# Sentral.net
KiCad netlist of a schematic drawn in EAGLE
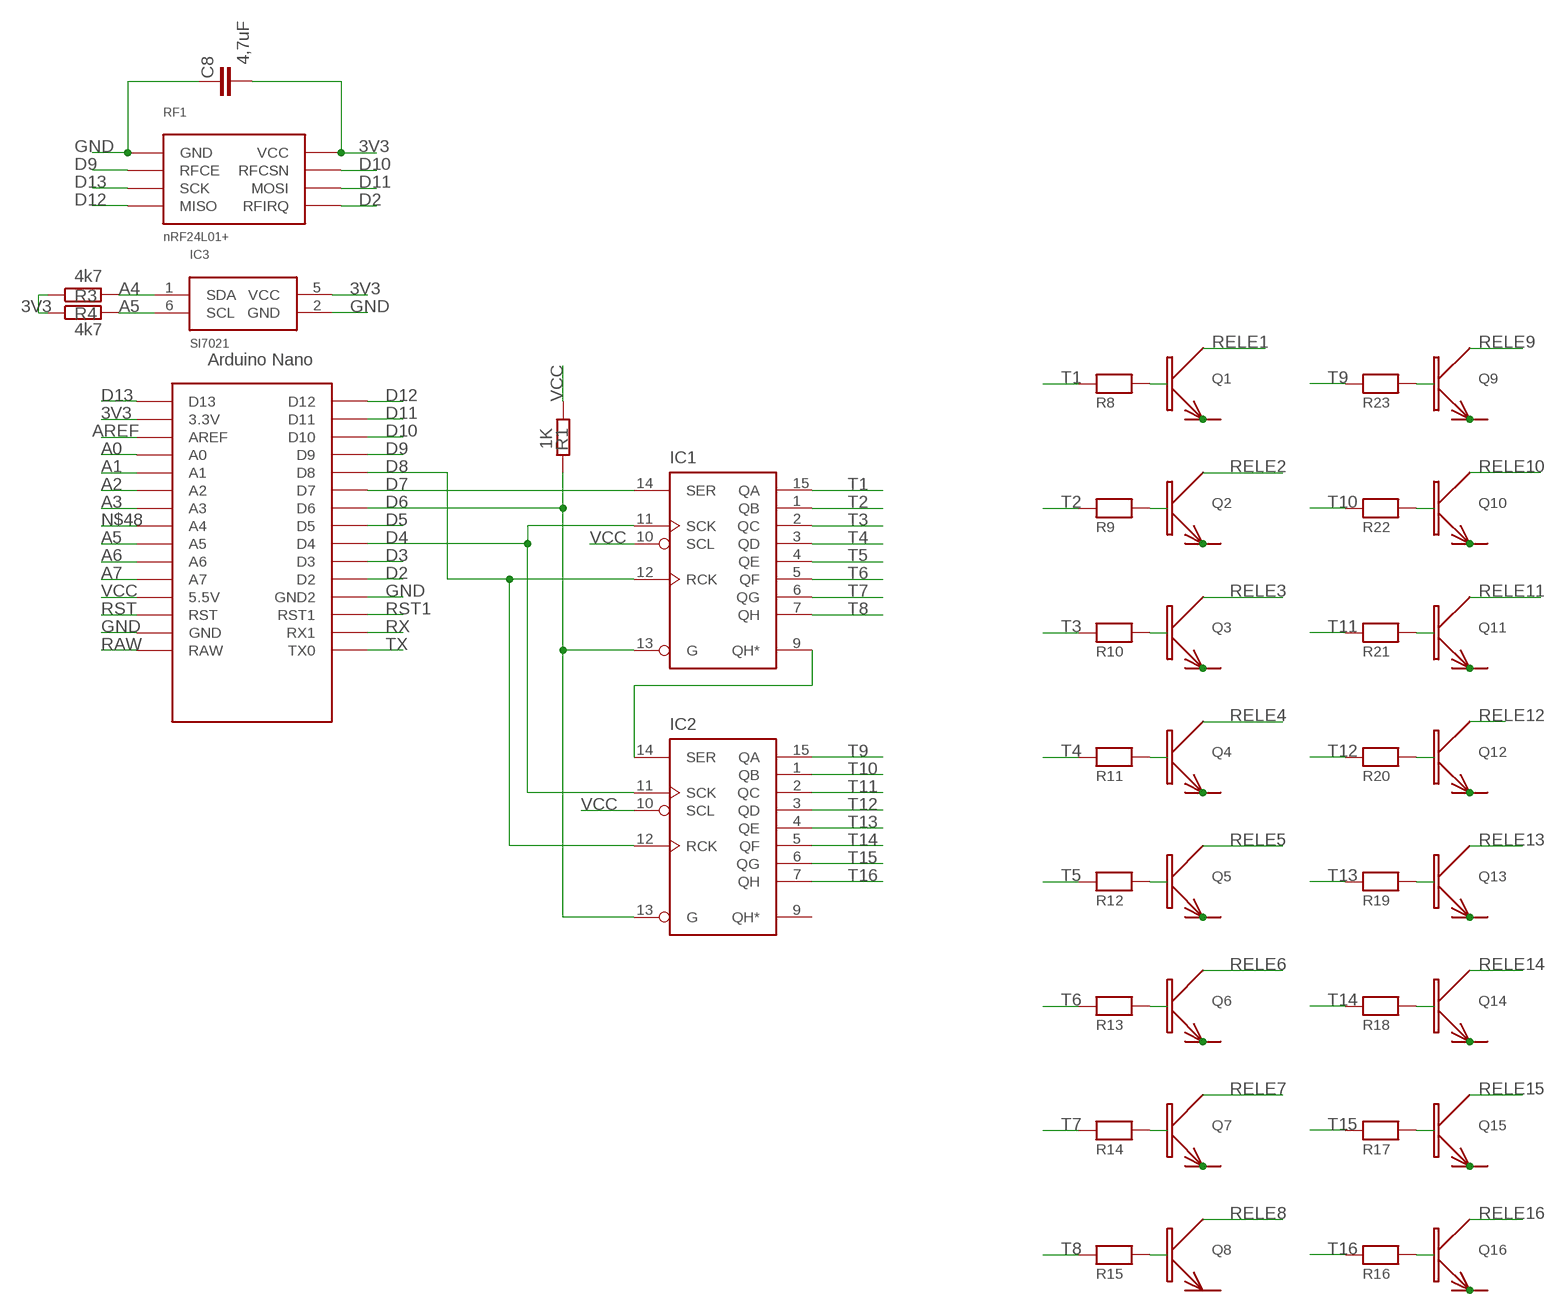
[diagram p0: schematic, sheet 1]
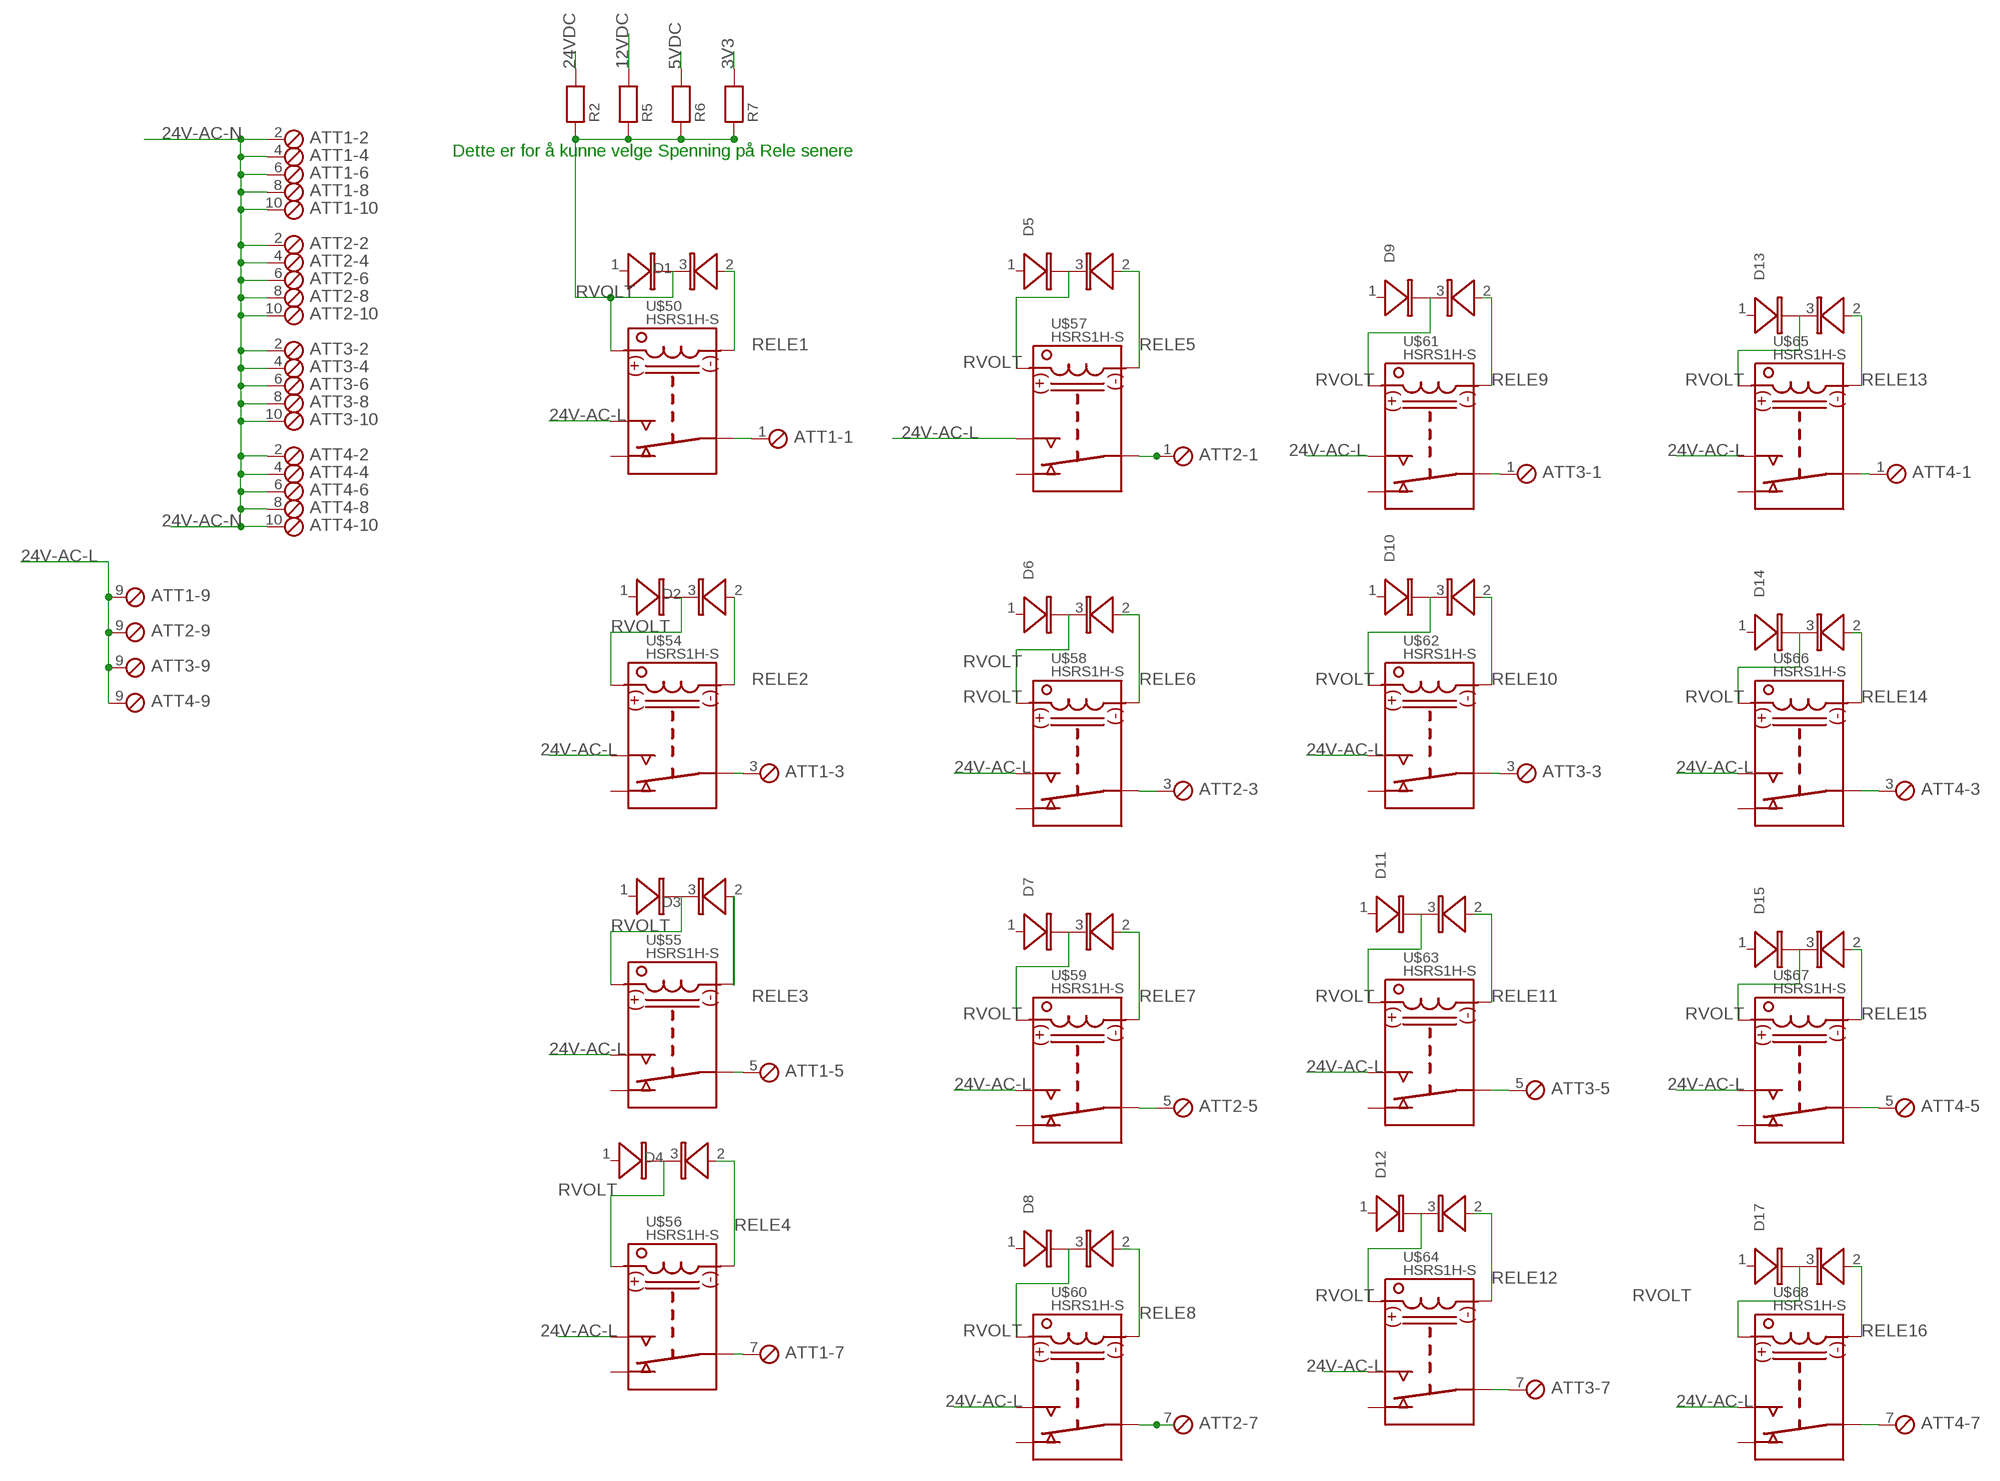
[diagram p1: schematic, sheet 2]

(export (version "E")
  (design (tool "Eeschema 10.0.6"))
  (components
    (comp (ref "C8")
      (value "4,7uF")
      (footprint "eagle-import:C4532")
      (libsource (lib "eagle-import") (part "C-EUC4532"))
    )
    (comp (ref "IC1")
      (value "74595")
      (footprint "eagle-import:SO-16")
      (libsource (lib "eagle-import") (part "74595"))
    )
    (comp (ref "IC2")
      (value "74595")
      (footprint "eagle-import:SO-16")
      (libsource (lib "eagle-import") (part "74595"))
    )
    (comp (ref "IC3")
      (value "SI7021")
      (footprint "eagle-import:DFN6")
      (libsource (lib "eagle-import") (part "SI7021"))
    )
    (comp (ref "Q1")
      (value "BC817")
      (footprint "eagle-import:SOT23")
      (libsource (lib "eagle-import") (part "BC817"))
    )
    (comp (ref "Q2")
      (value "BC817")
      (footprint "eagle-import:SOT23")
      (libsource (lib "eagle-import") (part "BC817"))
    )
    (comp (ref "Q3")
      (value "BC817")
      (footprint "eagle-import:SOT23")
      (libsource (lib "eagle-import") (part "BC817"))
    )
    (comp (ref "Q4")
      (value "BC817")
      (footprint "eagle-import:SOT23")
      (libsource (lib "eagle-import") (part "BC817"))
    )
    (comp (ref "Q5")
      (value "BC817")
      (footprint "eagle-import:SOT23")
      (libsource (lib "eagle-import") (part "BC817"))
    )
    (comp (ref "Q6")
      (value "BC817")
      (footprint "eagle-import:SOT23")
      (libsource (lib "eagle-import") (part "BC817"))
    )
    (comp (ref "Q7")
      (value "BC817")
      (footprint "eagle-import:SOT23")
      (libsource (lib "eagle-import") (part "BC817"))
    )
    (comp (ref "Q8")
      (value "BC817")
      (footprint "eagle-import:SOT23")
      (libsource (lib "eagle-import") (part "BC817"))
    )
    (comp (ref "Q9")
      (value "BC817")
      (footprint "eagle-import:SOT23")
      (libsource (lib "eagle-import") (part "BC817"))
    )
    (comp (ref "Q10")
      (value "BC817")
      (footprint "eagle-import:SOT23")
      (libsource (lib "eagle-import") (part "BC817"))
    )
    (comp (ref "Q11")
      (value "BC817")
      (footprint "eagle-import:SOT23")
      (libsource (lib "eagle-import") (part "BC817"))
    )
    (comp (ref "Q12")
      (value "BC817")
      (footprint "eagle-import:SOT23")
      (libsource (lib "eagle-import") (part "BC817"))
    )
    (comp (ref "Q13")
      (value "BC817")
      (footprint "eagle-import:SOT23")
      (libsource (lib "eagle-import") (part "BC817"))
    )
    (comp (ref "Q14")
      (value "BC817")
      (footprint "eagle-import:SOT23")
      (libsource (lib "eagle-import") (part "BC817"))
    )
    (comp (ref "Q15")
      (value "BC817")
      (footprint "eagle-import:SOT23")
      (libsource (lib "eagle-import") (part "BC817"))
    )
    (comp (ref "Q16")
      (value "BC817")
      (footprint "eagle-import:SOT23")
      (libsource (lib "eagle-import") (part "BC817"))
    )
    (comp (ref "R1")
      (value "1K")
      (footprint "eagle-import:R0805")
      (libsource (lib "eagle-import") (part "R-EU_R0805"))
    )
    (comp (ref "R3")
      (value "4k7")
      (footprint "eagle-import:R0805")
      (libsource (lib "eagle-import") (part "R-EU_R0805"))
    )
    (comp (ref "R4")
      (value "4k7")
      (footprint "eagle-import:R0805")
      (libsource (lib "eagle-import") (part "R-EU_R0805"))
    )
    (comp (ref "R8")
      (value "RES-A")
      (footprint "eagle-import:A")
      (libsource (lib "eagle-import") (part "RES-A"))
    )
    (comp (ref "R9")
      (value "RES-A")
      (footprint "eagle-import:A")
      (libsource (lib "eagle-import") (part "RES-A"))
    )
    (comp (ref "R10")
      (value "RES-A")
      (footprint "eagle-import:A")
      (libsource (lib "eagle-import") (part "RES-A"))
    )
    (comp (ref "R11")
      (value "RES-A")
      (footprint "eagle-import:A")
      (libsource (lib "eagle-import") (part "RES-A"))
    )
    (comp (ref "R12")
      (value "RES-A")
      (footprint "eagle-import:A")
      (libsource (lib "eagle-import") (part "RES-A"))
    )
    (comp (ref "R13")
      (value "RES-A")
      (footprint "eagle-import:A")
      (libsource (lib "eagle-import") (part "RES-A"))
    )
    (comp (ref "R14")
      (value "RES-A")
      (footprint "eagle-import:A")
      (libsource (lib "eagle-import") (part "RES-A"))
    )
    (comp (ref "R15")
      (value "RES-A")
      (footprint "eagle-import:A")
      (libsource (lib "eagle-import") (part "RES-A"))
    )
    (comp (ref "R16")
      (value "RES-A")
      (footprint "eagle-import:A")
      (libsource (lib "eagle-import") (part "RES-A"))
    )
    (comp (ref "R17")
      (value "RES-A")
      (footprint "eagle-import:A")
      (libsource (lib "eagle-import") (part "RES-A"))
    )
    (comp (ref "R18")
      (value "RES-A")
      (footprint "eagle-import:A")
      (libsource (lib "eagle-import") (part "RES-A"))
    )
    (comp (ref "R19")
      (value "RES-A")
      (footprint "eagle-import:A")
      (libsource (lib "eagle-import") (part "RES-A"))
    )
    (comp (ref "R20")
      (value "RES-A")
      (footprint "eagle-import:A")
      (libsource (lib "eagle-import") (part "RES-A"))
    )
    (comp (ref "R21")
      (value "RES-A")
      (footprint "eagle-import:A")
      (libsource (lib "eagle-import") (part "RES-A"))
    )
    (comp (ref "R22")
      (value "RES-A")
      (footprint "eagle-import:A")
      (libsource (lib "eagle-import") (part "RES-A"))
    )
    (comp (ref "R23")
      (value "RES-A")
      (footprint "eagle-import:A")
      (libsource (lib "eagle-import") (part "RES-A"))
    )
    (comp (ref "RF1")
      (value "nRF24L01+")
      (footprint "eagle-import:2X4-2.54MM")
      (libsource (lib "eagle-import") (part "NRF24L01"))
    )
    (comp (ref "U$1")
      (value "NANO")
      (footprint "eagle-import:NANO")
      (libsource (lib "eagle-import") (part "NANO"))
    )
    (comp (ref "ATT1")
      (value "MPT10")
      (footprint "eagle-import:10POL254")
      (libsource (lib "eagle-import") (part "MPT10"))
    )
    (comp (ref "ATT2")
      (value "MPT10")
      (footprint "eagle-import:10POL254")
      (libsource (lib "eagle-import") (part "MPT10"))
    )
    (comp (ref "ATT3")
      (value "MPT10")
      (footprint "eagle-import:10POL254")
      (libsource (lib "eagle-import") (part "MPT10"))
    )
    (comp (ref "ATT4")
      (value "MPT10")
      (footprint "eagle-import:10POL254")
      (libsource (lib "eagle-import") (part "MPT10"))
    )
    (comp (ref "D1")
      (value "BAV70")
      (footprint "eagle-import:SOT23")
      (libsource (lib "eagle-import") (part "BAV70"))
    )
    (comp (ref "D2")
      (value "BAV70")
      (footprint "eagle-import:SOT23")
      (libsource (lib "eagle-import") (part "BAV70"))
    )
    (comp (ref "D3")
      (value "BAV70")
      (footprint "eagle-import:SOT23")
      (libsource (lib "eagle-import") (part "BAV70"))
    )
    (comp (ref "D4")
      (value "BAV70")
      (footprint "eagle-import:SOT23")
      (libsource (lib "eagle-import") (part "BAV70"))
    )
    (comp (ref "D5")
      (value "BAV70")
      (footprint "eagle-import:SOT23")
      (libsource (lib "eagle-import") (part "BAV70"))
    )
    (comp (ref "D6")
      (value "BAV70")
      (footprint "eagle-import:SOT23")
      (libsource (lib "eagle-import") (part "BAV70"))
    )
    (comp (ref "D7")
      (value "BAV70")
      (footprint "eagle-import:SOT23")
      (libsource (lib "eagle-import") (part "BAV70"))
    )
    (comp (ref "D8")
      (value "BAV70")
      (footprint "eagle-import:SOT23")
      (libsource (lib "eagle-import") (part "BAV70"))
    )
    (comp (ref "D9")
      (value "BAV70")
      (footprint "eagle-import:SOT23")
      (libsource (lib "eagle-import") (part "BAV70"))
    )
    (comp (ref "D10")
      (value "BAV70")
      (footprint "eagle-import:SOT23")
      (libsource (lib "eagle-import") (part "BAV70"))
    )
    (comp (ref "D11")
      (value "BAV70")
      (footprint "eagle-import:SOT23")
      (libsource (lib "eagle-import") (part "BAV70"))
    )
    (comp (ref "D12")
      (value "BAV70")
      (footprint "eagle-import:SOT23")
      (libsource (lib "eagle-import") (part "BAV70"))
    )
    (comp (ref "D13")
      (value "BAV70")
      (footprint "eagle-import:SOT23")
      (libsource (lib "eagle-import") (part "BAV70"))
    )
    (comp (ref "D14")
      (value "BAV70")
      (footprint "eagle-import:SOT23")
      (libsource (lib "eagle-import") (part "BAV70"))
    )
    (comp (ref "D15")
      (value "BAV70")
      (footprint "eagle-import:SOT23")
      (libsource (lib "eagle-import") (part "BAV70"))
    )
    (comp (ref "D17")
      (value "BAV70")
      (footprint "eagle-import:SOT23")
      (libsource (lib "eagle-import") (part "BAV70"))
    )
    (comp (ref "R2")
      (value "RES-C")
      (footprint "eagle-import:C")
      (libsource (lib "eagle-import") (part "RES-C"))
    )
    (comp (ref "R5")
      (value "RES-C")
      (footprint "eagle-import:C")
      (libsource (lib "eagle-import") (part "RES-C"))
    )
    (comp (ref "R6")
      (value "RES-C")
      (footprint "eagle-import:C")
      (libsource (lib "eagle-import") (part "RES-C"))
    )
    (comp (ref "R7")
      (value "RES-C")
      (footprint "eagle-import:C")
      (libsource (lib "eagle-import") (part "RES-C"))
    )
    (comp (ref "U$50")
      (value "HSRS1H-S")
      (footprint "eagle-import:DIL12RLY")
      (libsource (lib "eagle-import") (part "HSRS1H-S"))
    )
    (comp (ref "U$54")
      (value "HSRS1H-S")
      (footprint "eagle-import:DIL12RLY")
      (libsource (lib "eagle-import") (part "HSRS1H-S"))
    )
    (comp (ref "U$55")
      (value "HSRS1H-S")
      (footprint "eagle-import:DIL12RLY")
      (libsource (lib "eagle-import") (part "HSRS1H-S"))
    )
    (comp (ref "U$56")
      (value "HSRS1H-S")
      (footprint "eagle-import:DIL12RLY")
      (libsource (lib "eagle-import") (part "HSRS1H-S"))
    )
    (comp (ref "U$57")
      (value "HSRS1H-S")
      (footprint "eagle-import:DIL12RLY")
      (libsource (lib "eagle-import") (part "HSRS1H-S"))
    )
    (comp (ref "U$58")
      (value "HSRS1H-S")
      (footprint "eagle-import:DIL12RLY")
      (libsource (lib "eagle-import") (part "HSRS1H-S"))
    )
    (comp (ref "U$59")
      (value "HSRS1H-S")
      (footprint "eagle-import:DIL12RLY")
      (libsource (lib "eagle-import") (part "HSRS1H-S"))
    )
    (comp (ref "U$60")
      (value "HSRS1H-S")
      (footprint "eagle-import:DIL12RLY")
      (libsource (lib "eagle-import") (part "HSRS1H-S"))
    )
    (comp (ref "U$61")
      (value "HSRS1H-S")
      (footprint "eagle-import:DIL12RLY")
      (libsource (lib "eagle-import") (part "HSRS1H-S"))
    )
    (comp (ref "U$62")
      (value "HSRS1H-S")
      (footprint "eagle-import:DIL12RLY")
      (libsource (lib "eagle-import") (part "HSRS1H-S"))
    )
    (comp (ref "U$63")
      (value "HSRS1H-S")
      (footprint "eagle-import:DIL12RLY")
      (libsource (lib "eagle-import") (part "HSRS1H-S"))
    )
    (comp (ref "U$64")
      (value "HSRS1H-S")
      (footprint "eagle-import:DIL12RLY")
      (libsource (lib "eagle-import") (part "HSRS1H-S"))
    )
    (comp (ref "U$65")
      (value "HSRS1H-S")
      (footprint "eagle-import:DIL12RLY")
      (libsource (lib "eagle-import") (part "HSRS1H-S"))
    )
    (comp (ref "U$66")
      (value "HSRS1H-S")
      (footprint "eagle-import:DIL12RLY")
      (libsource (lib "eagle-import") (part "HSRS1H-S"))
    )
    (comp (ref "U$67")
      (value "HSRS1H-S")
      (footprint "eagle-import:DIL12RLY")
      (libsource (lib "eagle-import") (part "HSRS1H-S"))
    )
    (comp (ref "U$68")
      (value "HSRS1H-S")
      (footprint "eagle-import:DIL12RLY")
      (libsource (lib "eagle-import") (part "HSRS1H-S"))
    )
  )
  (nets
    (net (code "1") (name "3V3") (class "Default")
      (node (ref "C8") (pin "1") (pinfunction "1_1") (pintype "passive"))
      (node (ref "IC3") (pin "5") (pinfunction "VCC_5") (pintype "bidirectional"))
      (node (ref "R3") (pin "1") (pinfunction "1_1") (pintype "passive"))
      (node (ref "R4") (pin "1") (pinfunction "1_1") (pintype "passive"))
      (node (ref "R7") (pin "2") (pinfunction "2_2") (pintype "passive"))
      (node (ref "RF1") (pin "P$2") (pinfunction "VCC_P$2") (pintype "power_in"))
      (node (ref "U$1") (pin "3.3V") (pinfunction "3.3V_3.3V") (pintype "bidirectional"))
    )
    (net (code "2") (name "5VDC") (class "Default")
      (node (ref "R6") (pin "2") (pinfunction "2_2") (pintype "passive"))
    )
    (net (code "3") (name "12VDC") (class "Default")
      (node (ref "R5") (pin "2") (pinfunction "2_2") (pintype "passive"))
    )
    (net (code "4") (name "24V-AC-L") (class "Default")
      (node (ref "ATT1") (pin "9") (pinfunction "1_9") (pintype "passive"))
      (node (ref "ATT2") (pin "9") (pinfunction "1_9") (pintype "passive"))
      (node (ref "ATT3") (pin "9") (pinfunction "1_9") (pintype "passive"))
      (node (ref "ATT4") (pin "9") (pinfunction "1_9") (pintype "passive"))
      (node (ref "U$50") (pin "1") (pinfunction "1_1") (pintype "passive"))
      (node (ref "U$54") (pin "1") (pinfunction "1_1") (pintype "passive"))
      (node (ref "U$55") (pin "1") (pinfunction "1_1") (pintype "passive"))
      (node (ref "U$56") (pin "1") (pinfunction "1_1") (pintype "passive"))
      (node (ref "U$57") (pin "1") (pinfunction "1_1") (pintype "passive"))
      (node (ref "U$58") (pin "1") (pinfunction "1_1") (pintype "passive"))
      (node (ref "U$59") (pin "1") (pinfunction "1_1") (pintype "passive"))
      (node (ref "U$60") (pin "1") (pinfunction "1_1") (pintype "passive"))
      (node (ref "U$61") (pin "1") (pinfunction "1_1") (pintype "passive"))
      (node (ref "U$62") (pin "1") (pinfunction "1_1") (pintype "passive"))
      (node (ref "U$63") (pin "1") (pinfunction "1_1") (pintype "passive"))
      (node (ref "U$64") (pin "1") (pinfunction "1_1") (pintype "passive"))
      (node (ref "U$65") (pin "1") (pinfunction "1_1") (pintype "passive"))
      (node (ref "U$66") (pin "1") (pinfunction "1_1") (pintype "passive"))
      (node (ref "U$67") (pin "1") (pinfunction "1_1") (pintype "passive"))
      (node (ref "U$68") (pin "1") (pinfunction "1_1") (pintype "passive"))
    )
    (net (code "5") (name "24V-AC-N") (class "Default")
      (node (ref "ATT1") (pin "10") (pinfunction "1_10") (pintype "passive"))
      (node (ref "ATT1") (pin "2") (pinfunction "1_2") (pintype "passive"))
      (node (ref "ATT1") (pin "4") (pinfunction "1_4") (pintype "passive"))
      (node (ref "ATT1") (pin "6") (pinfunction "1_6") (pintype "passive"))
      (node (ref "ATT1") (pin "8") (pinfunction "1_8") (pintype "passive"))
      (node (ref "ATT2") (pin "10") (pinfunction "1_10") (pintype "passive"))
      (node (ref "ATT2") (pin "2") (pinfunction "1_2") (pintype "passive"))
      (node (ref "ATT2") (pin "4") (pinfunction "1_4") (pintype "passive"))
      (node (ref "ATT2") (pin "6") (pinfunction "1_6") (pintype "passive"))
      (node (ref "ATT2") (pin "8") (pinfunction "1_8") (pintype "passive"))
      (node (ref "ATT3") (pin "10") (pinfunction "1_10") (pintype "passive"))
      (node (ref "ATT3") (pin "2") (pinfunction "1_2") (pintype "passive"))
      (node (ref "ATT3") (pin "4") (pinfunction "1_4") (pintype "passive"))
      (node (ref "ATT3") (pin "6") (pinfunction "1_6") (pintype "passive"))
      (node (ref "ATT3") (pin "8") (pinfunction "1_8") (pintype "passive"))
      (node (ref "ATT4") (pin "10") (pinfunction "1_10") (pintype "passive"))
      (node (ref "ATT4") (pin "2") (pinfunction "1_2") (pintype "passive"))
      (node (ref "ATT4") (pin "4") (pinfunction "1_4") (pintype "passive"))
      (node (ref "ATT4") (pin "6") (pinfunction "1_6") (pintype "passive"))
      (node (ref "ATT4") (pin "8") (pinfunction "1_8") (pintype "passive"))
    )
    (net (code "6") (name "24VDC") (class "Default")
      (node (ref "R2") (pin "2") (pinfunction "2_2") (pintype "passive"))
    )
    (net (code "7") (name "A0") (class "Default")
      (node (ref "U$1") (pin "A0") (pinfunction "A0_A0") (pintype "bidirectional"))
    )
    (net (code "8") (name "A1") (class "Default")
      (node (ref "U$1") (pin "A1") (pinfunction "A1_A1") (pintype "bidirectional"))
    )
    (net (code "9") (name "A2") (class "Default")
      (node (ref "U$1") (pin "A2") (pinfunction "A2_A2") (pintype "bidirectional"))
    )
    (net (code "10") (name "A3") (class "Default")
      (node (ref "U$1") (pin "A3") (pinfunction "A3_A3") (pintype "bidirectional"))
    )
    (net (code "11") (name "A4") (class "Default")
      (node (ref "IC3") (pin "1") (pinfunction "SDA_1") (pintype "bidirectional"))
      (node (ref "R3") (pin "2") (pinfunction "2_2") (pintype "passive"))
    )
    (net (code "12") (name "A5") (class "Default")
      (node (ref "IC3") (pin "6") (pinfunction "SCL_6") (pintype "bidirectional"))
      (node (ref "R4") (pin "2") (pinfunction "2_2") (pintype "passive"))
      (node (ref "U$1") (pin "A5") (pinfunction "A5_A5") (pintype "bidirectional"))
    )
    (net (code "13") (name "A6") (class "Default")
      (node (ref "U$1") (pin "A6") (pinfunction "A6_A6") (pintype "bidirectional"))
    )
    (net (code "14") (name "A7") (class "Default")
      (node (ref "U$1") (pin "A7") (pinfunction "A7_A7") (pintype "bidirectional"))
    )
    (net (code "15") (name "AREF") (class "Default")
      (node (ref "U$1") (pin "AREF") (pinfunction "AREF_AREF") (pintype "bidirectional"))
    )
    (net (code "16") (name "D2") (class "Default")
      (node (ref "RF1") (pin "P$8") (pinfunction "RFIRQ_P$8") (pintype "output"))
      (node (ref "U$1") (pin "D2") (pinfunction "D2_D2") (pintype "bidirectional"))
    )
    (net (code "17") (name "D3") (class "Default")
      (node (ref "U$1") (pin "D3") (pinfunction "D3_D3") (pintype "bidirectional"))
    )
    (net (code "18") (name "D4") (class "Default")
      (node (ref "IC1") (pin "11") (pinfunction "SCK_11") (pintype "input"))
      (node (ref "IC2") (pin "11") (pinfunction "SCK_11") (pintype "input"))
      (node (ref "U$1") (pin "D4") (pinfunction "D4_D4") (pintype "bidirectional"))
    )
    (net (code "19") (name "D5") (class "Default")
      (node (ref "U$1") (pin "D5") (pinfunction "D5_D5") (pintype "bidirectional"))
    )
    (net (code "20") (name "D6") (class "Default")
      (node (ref "IC1") (pin "13") (pinfunction "G_13") (pintype "input"))
      (node (ref "IC2") (pin "13") (pinfunction "G_13") (pintype "input"))
      (node (ref "R1") (pin "2") (pinfunction "2_2") (pintype "passive"))
      (node (ref "U$1") (pin "D6") (pinfunction "D6_D6") (pintype "bidirectional"))
    )
    (net (code "21") (name "D7") (class "Default")
      (node (ref "IC1") (pin "14") (pinfunction "SER_14") (pintype "input"))
      (node (ref "U$1") (pin "D7") (pinfunction "D7_D7") (pintype "bidirectional"))
    )
    (net (code "22") (name "D8") (class "Default")
      (node (ref "IC1") (pin "12") (pinfunction "RCK_12") (pintype "input"))
      (node (ref "IC2") (pin "12") (pinfunction "RCK_12") (pintype "input"))
      (node (ref "U$1") (pin "D8") (pinfunction "D8_D8") (pintype "bidirectional"))
    )
    (net (code "23") (name "D9") (class "Default")
      (node (ref "RF1") (pin "P$3") (pinfunction "RFCE_P$3") (pintype "input"))
      (node (ref "U$1") (pin "D9") (pinfunction "D9_D9") (pintype "bidirectional"))
    )
    (net (code "24") (name "D10") (class "Default")
      (node (ref "RF1") (pin "P$4") (pinfunction "RFCSN_P$4") (pintype "bidirectional"))
      (node (ref "U$1") (pin "D10") (pinfunction "D10_D10") (pintype "bidirectional"))
    )
    (net (code "25") (name "D11") (class "Default")
      (node (ref "RF1") (pin "P$6") (pinfunction "MOSI_P$6") (pintype "bidirectional"))
      (node (ref "U$1") (pin "D11") (pinfunction "D11_D11") (pintype "bidirectional"))
    )
    (net (code "26") (name "D12") (class "Default")
      (node (ref "RF1") (pin "P$7") (pinfunction "MISO_P$7") (pintype "bidirectional"))
      (node (ref "U$1") (pin "D12") (pinfunction "D12_D12") (pintype "bidirectional"))
    )
    (net (code "27") (name "D13") (class "Default")
      (node (ref "RF1") (pin "P$5") (pinfunction "SCK_P$5") (pintype "input"))
      (node (ref "U$1") (pin "D13") (pinfunction "D13_D13") (pintype "bidirectional"))
    )
    (net (code "28") (name "GND") (class "Default")
      (node (ref "C8") (pin "2") (pinfunction "2_2") (pintype "passive"))
      (node (ref "IC3") (pin "2") (pinfunction "GND_2") (pintype "bidirectional"))
      (node (ref "Q1") (pin "1") (pinfunction "E_1") (pintype "passive"))
      (node (ref "Q10") (pin "1") (pinfunction "E_1") (pintype "passive"))
      (node (ref "Q11") (pin "1") (pinfunction "E_1") (pintype "passive"))
      (node (ref "Q12") (pin "1") (pinfunction "E_1") (pintype "passive"))
      (node (ref "Q13") (pin "1") (pinfunction "E_1") (pintype "passive"))
      (node (ref "Q14") (pin "1") (pinfunction "E_1") (pintype "passive"))
      (node (ref "Q15") (pin "1") (pinfunction "E_1") (pintype "passive"))
      (node (ref "Q16") (pin "1") (pinfunction "E_1") (pintype "passive"))
      (node (ref "Q2") (pin "1") (pinfunction "E_1") (pintype "passive"))
      (node (ref "Q3") (pin "1") (pinfunction "E_1") (pintype "passive"))
      (node (ref "Q4") (pin "1") (pinfunction "E_1") (pintype "passive"))
      (node (ref "Q5") (pin "1") (pinfunction "E_1") (pintype "passive"))
      (node (ref "Q6") (pin "1") (pinfunction "E_1") (pintype "passive"))
      (node (ref "Q7") (pin "1") (pinfunction "E_1") (pintype "passive"))
      (node (ref "Q8") (pin "1") (pinfunction "E_1") (pintype "passive"))
      (node (ref "Q9") (pin "1") (pinfunction "E_1") (pintype "passive"))
      (node (ref "RF1") (pin "P$1") (pinfunction "GND_P$1") (pintype "power_in"))
      (node (ref "U$1") (pin "GND") (pinfunction "GND_GND") (pintype "bidirectional"))
      (node (ref "U$1") (pin "GND1") (pinfunction "GND2_GND1") (pintype "bidirectional"))
    )
    (net (code "29") (name "N$48") (class "Default")
      (node (ref "U$1") (pin "A4") (pinfunction "A4_A4") (pintype "bidirectional"))
    )
    (net (code "30") (name "Net-(ATT1-Pad1)") (class "Default")
      (node (ref "ATT1") (pin "1") (pinfunction "1_1") (pintype "passive"))
      (node (ref "U$50") (pin "6") (pinfunction "6,7_6") (pintype "passive"))
      (node (ref "U$50") (pin "7") (pinfunction "6,7_7") (pintype "passive"))
    )
    (net (code "31") (name "Net-(ATT1D-1)") (class "Default")
      (node (ref "ATT1") (pin "3") (pinfunction "1_3") (pintype "passive"))
      (node (ref "U$54") (pin "6") (pinfunction "6,7_6") (pintype "passive"))
      (node (ref "U$54") (pin "7") (pinfunction "6,7_7") (pintype "passive"))
    )
    (net (code "32") (name "Net-(ATT1F-1)") (class "Default")
      (node (ref "ATT1") (pin "5") (pinfunction "1_5") (pintype "passive"))
      (node (ref "U$55") (pin "6") (pinfunction "6,7_6") (pintype "passive"))
      (node (ref "U$55") (pin "7") (pinfunction "6,7_7") (pintype "passive"))
    )
    (net (code "33") (name "Net-(ATT1H-1)") (class "Default")
      (node (ref "ATT1") (pin "7") (pinfunction "1_7") (pintype "passive"))
      (node (ref "U$56") (pin "6") (pinfunction "6,7_6") (pintype "passive"))
      (node (ref "U$56") (pin "7") (pinfunction "6,7_7") (pintype "passive"))
    )
    (net (code "34") (name "Net-(ATT2-Pad1)") (class "Default")
      (node (ref "ATT2") (pin "1") (pinfunction "1_1") (pintype "passive"))
      (node (ref "U$57") (pin "6") (pinfunction "6,7_6") (pintype "passive"))
      (node (ref "U$57") (pin "7") (pinfunction "6,7_7") (pintype "passive"))
    )
    (net (code "35") (name "Net-(ATT2D-1)") (class "Default")
      (node (ref "ATT2") (pin "3") (pinfunction "1_3") (pintype "passive"))
      (node (ref "U$58") (pin "6") (pinfunction "6,7_6") (pintype "passive"))
      (node (ref "U$58") (pin "7") (pinfunction "6,7_7") (pintype "passive"))
    )
    (net (code "36") (name "Net-(ATT2F-1)") (class "Default")
      (node (ref "ATT2") (pin "5") (pinfunction "1_5") (pintype "passive"))
      (node (ref "U$59") (pin "6") (pinfunction "6,7_6") (pintype "passive"))
      (node (ref "U$59") (pin "7") (pinfunction "6,7_7") (pintype "passive"))
    )
    (net (code "37") (name "Net-(ATT2H-1)") (class "Default")
      (node (ref "ATT2") (pin "7") (pinfunction "1_7") (pintype "passive"))
      (node (ref "U$60") (pin "6") (pinfunction "6,7_6") (pintype "passive"))
      (node (ref "U$60") (pin "7") (pinfunction "6,7_7") (pintype "passive"))
    )
    (net (code "38") (name "Net-(ATT3-Pad1)") (class "Default")
      (node (ref "ATT3") (pin "1") (pinfunction "1_1") (pintype "passive"))
      (node (ref "U$61") (pin "6") (pinfunction "6,7_6") (pintype "passive"))
      (node (ref "U$61") (pin "7") (pinfunction "6,7_7") (pintype "passive"))
    )
    (net (code "39") (name "Net-(ATT3D-1)") (class "Default")
      (node (ref "ATT3") (pin "3") (pinfunction "1_3") (pintype "passive"))
      (node (ref "U$62") (pin "6") (pinfunction "6,7_6") (pintype "passive"))
      (node (ref "U$62") (pin "7") (pinfunction "6,7_7") (pintype "passive"))
    )
    (net (code "40") (name "Net-(ATT3F-1)") (class "Default")
      (node (ref "ATT3") (pin "5") (pinfunction "1_5") (pintype "passive"))
      (node (ref "U$63") (pin "6") (pinfunction "6,7_6") (pintype "passive"))
      (node (ref "U$63") (pin "7") (pinfunction "6,7_7") (pintype "passive"))
    )
    (net (code "41") (name "Net-(ATT3H-1)") (class "Default")
      (node (ref "ATT3") (pin "7") (pinfunction "1_7") (pintype "passive"))
      (node (ref "U$64") (pin "6") (pinfunction "6,7_6") (pintype "passive"))
      (node (ref "U$64") (pin "7") (pinfunction "6,7_7") (pintype "passive"))
    )
    (net (code "42") (name "Net-(ATT4-Pad1)") (class "Default")
      (node (ref "ATT4") (pin "1") (pinfunction "1_1") (pintype "passive"))
      (node (ref "U$65") (pin "6") (pinfunction "6,7_6") (pintype "passive"))
      (node (ref "U$65") (pin "7") (pinfunction "6,7_7") (pintype "passive"))
    )
    (net (code "43") (name "Net-(ATT4D-1)") (class "Default")
      (node (ref "ATT4") (pin "3") (pinfunction "1_3") (pintype "passive"))
      (node (ref "U$66") (pin "6") (pinfunction "6,7_6") (pintype "passive"))
      (node (ref "U$66") (pin "7") (pinfunction "6,7_7") (pintype "passive"))
    )
    (net (code "44") (name "Net-(ATT4F-1)") (class "Default")
      (node (ref "ATT4") (pin "5") (pinfunction "1_5") (pintype "passive"))
      (node (ref "U$67") (pin "6") (pinfunction "6,7_6") (pintype "passive"))
      (node (ref "U$67") (pin "7") (pinfunction "6,7_7") (pintype "passive"))
    )
    (net (code "45") (name "Net-(ATT4H-1)") (class "Default")
      (node (ref "ATT4") (pin "7") (pinfunction "1_7") (pintype "passive"))
      (node (ref "U$68") (pin "6") (pinfunction "6,7_6") (pintype "passive"))
      (node (ref "U$68") (pin "7") (pinfunction "6,7_7") (pintype "passive"))
    )
    (net (code "46") (name "Net-(IC1A-QH*)") (class "Default")
      (node (ref "IC1") (pin "9") (pinfunction "QH*_9") (pintype "tri_state"))
      (node (ref "IC2") (pin "14") (pinfunction "SER_14") (pintype "input"))
    )
    (net (code "47") (name "Net-(Q1-B)") (class "Default")
      (node (ref "Q1") (pin "2") (pinfunction "B_2") (pintype "passive"))
      (node (ref "R8") (pin "2") (pinfunction "2_2") (pintype "passive"))
    )
    (net (code "48") (name "Net-(Q2-B)") (class "Default")
      (node (ref "Q2") (pin "2") (pinfunction "B_2") (pintype "passive"))
      (node (ref "R9") (pin "2") (pinfunction "2_2") (pintype "passive"))
    )
    (net (code "49") (name "Net-(Q3-B)") (class "Default")
      (node (ref "Q3") (pin "2") (pinfunction "B_2") (pintype "passive"))
      (node (ref "R10") (pin "2") (pinfunction "2_2") (pintype "passive"))
    )
    (net (code "50") (name "Net-(Q4-B)") (class "Default")
      (node (ref "Q4") (pin "2") (pinfunction "B_2") (pintype "passive"))
      (node (ref "R11") (pin "2") (pinfunction "2_2") (pintype "passive"))
    )
    (net (code "51") (name "Net-(Q5-B)") (class "Default")
      (node (ref "Q5") (pin "2") (pinfunction "B_2") (pintype "passive"))
      (node (ref "R12") (pin "2") (pinfunction "2_2") (pintype "passive"))
    )
    (net (code "52") (name "Net-(Q6-B)") (class "Default")
      (node (ref "Q6") (pin "2") (pinfunction "B_2") (pintype "passive"))
      (node (ref "R13") (pin "2") (pinfunction "2_2") (pintype "passive"))
    )
    (net (code "53") (name "Net-(Q7-B)") (class "Default")
      (node (ref "Q7") (pin "2") (pinfunction "B_2") (pintype "passive"))
      (node (ref "R14") (pin "2") (pinfunction "2_2") (pintype "passive"))
    )
    (net (code "54") (name "Net-(Q8-B)") (class "Default")
      (node (ref "Q8") (pin "2") (pinfunction "B_2") (pintype "passive"))
      (node (ref "R15") (pin "2") (pinfunction "2_2") (pintype "passive"))
    )
    (net (code "55") (name "Net-(Q9-B)") (class "Default")
      (node (ref "Q9") (pin "2") (pinfunction "B_2") (pintype "passive"))
      (node (ref "R23") (pin "2") (pinfunction "2_2") (pintype "passive"))
    )
    (net (code "56") (name "Net-(Q10-B)") (class "Default")
      (node (ref "Q10") (pin "2") (pinfunction "B_2") (pintype "passive"))
      (node (ref "R22") (pin "2") (pinfunction "2_2") (pintype "passive"))
    )
    (net (code "57") (name "Net-(Q11-B)") (class "Default")
      (node (ref "Q11") (pin "2") (pinfunction "B_2") (pintype "passive"))
      (node (ref "R21") (pin "2") (pinfunction "2_2") (pintype "passive"))
    )
    (net (code "58") (name "Net-(Q12-B)") (class "Default")
      (node (ref "Q12") (pin "2") (pinfunction "B_2") (pintype "passive"))
      (node (ref "R20") (pin "2") (pinfunction "2_2") (pintype "passive"))
    )
    (net (code "59") (name "Net-(Q13-B)") (class "Default")
      (node (ref "Q13") (pin "2") (pinfunction "B_2") (pintype "passive"))
      (node (ref "R19") (pin "2") (pinfunction "2_2") (pintype "passive"))
    )
    (net (code "60") (name "Net-(Q14-B)") (class "Default")
      (node (ref "Q14") (pin "2") (pinfunction "B_2") (pintype "passive"))
      (node (ref "R18") (pin "2") (pinfunction "2_2") (pintype "passive"))
    )
    (net (code "61") (name "Net-(Q15-B)") (class "Default")
      (node (ref "Q15") (pin "2") (pinfunction "B_2") (pintype "passive"))
      (node (ref "R17") (pin "2") (pinfunction "2_2") (pintype "passive"))
    )
    (net (code "62") (name "Net-(Q16-B)") (class "Default")
      (node (ref "Q16") (pin "2") (pinfunction "B_2") (pintype "passive"))
      (node (ref "R16") (pin "2") (pinfunction "2_2") (pintype "passive"))
    )
    (net (code "63") (name "RAW") (class "Default")
      (node (ref "U$1") (pin "RAW") (pinfunction "RAW_RAW") (pintype "bidirectional"))
    )
    (net (code "64") (name "RELE1") (class "Default")
      (node (ref "D1") (pin "2") (pinfunction "A2_2") (pintype "passive"))
      (node (ref "Q1") (pin "3") (pinfunction "C_3") (pintype "passive"))
      (node (ref "U$50") (pin "11") (pinfunction "11_11") (pintype "passive"))
    )
    (net (code "65") (name "RELE2") (class "Default")
      (node (ref "D2") (pin "2") (pinfunction "A2_2") (pintype "passive"))
      (node (ref "Q2") (pin "3") (pinfunction "C_3") (pintype "passive"))
      (node (ref "U$54") (pin "11") (pinfunction "11_11") (pintype "passive"))
    )
    (net (code "66") (name "RELE3") (class "Default")
      (node (ref "D3") (pin "2") (pinfunction "A2_2") (pintype "passive"))
      (node (ref "Q3") (pin "3") (pinfunction "C_3") (pintype "passive"))
      (node (ref "U$55") (pin "11") (pinfunction "11_11") (pintype "passive"))
    )
    (net (code "67") (name "RELE4") (class "Default")
      (node (ref "D4") (pin "2") (pinfunction "A2_2") (pintype "passive"))
      (node (ref "Q4") (pin "3") (pinfunction "C_3") (pintype "passive"))
      (node (ref "U$56") (pin "11") (pinfunction "11_11") (pintype "passive"))
    )
    (net (code "68") (name "RELE5") (class "Default")
      (node (ref "D5") (pin "2") (pinfunction "A2_2") (pintype "passive"))
      (node (ref "Q5") (pin "3") (pinfunction "C_3") (pintype "passive"))
      (node (ref "U$57") (pin "11") (pinfunction "11_11") (pintype "passive"))
    )
    (net (code "69") (name "RELE6") (class "Default")
      (node (ref "D6") (pin "2") (pinfunction "A2_2") (pintype "passive"))
      (node (ref "Q6") (pin "3") (pinfunction "C_3") (pintype "passive"))
      (node (ref "U$58") (pin "11") (pinfunction "11_11") (pintype "passive"))
    )
    (net (code "70") (name "RELE7") (class "Default")
      (node (ref "D7") (pin "2") (pinfunction "A2_2") (pintype "passive"))
      (node (ref "Q7") (pin "3") (pinfunction "C_3") (pintype "passive"))
      (node (ref "U$59") (pin "11") (pinfunction "11_11") (pintype "passive"))
    )
    (net (code "71") (name "RELE8") (class "Default")
      (node (ref "D8") (pin "2") (pinfunction "A2_2") (pintype "passive"))
      (node (ref "Q8") (pin "3") (pinfunction "C_3") (pintype "passive"))
      (node (ref "U$60") (pin "11") (pinfunction "11_11") (pintype "passive"))
    )
    (net (code "72") (name "RELE9") (class "Default")
      (node (ref "D9") (pin "2") (pinfunction "A2_2") (pintype "passive"))
      (node (ref "Q9") (pin "3") (pinfunction "C_3") (pintype "passive"))
      (node (ref "U$61") (pin "11") (pinfunction "11_11") (pintype "passive"))
    )
    (net (code "73") (name "RELE10") (class "Default")
      (node (ref "D10") (pin "2") (pinfunction "A2_2") (pintype "passive"))
      (node (ref "Q10") (pin "3") (pinfunction "C_3") (pintype "passive"))
      (node (ref "U$62") (pin "11") (pinfunction "11_11") (pintype "passive"))
    )
    (net (code "74") (name "RELE11") (class "Default")
      (node (ref "D11") (pin "2") (pinfunction "A2_2") (pintype "passive"))
      (node (ref "Q11") (pin "3") (pinfunction "C_3") (pintype "passive"))
      (node (ref "U$63") (pin "11") (pinfunction "11_11") (pintype "passive"))
    )
    (net (code "75") (name "RELE12") (class "Default")
      (node (ref "D12") (pin "2") (pinfunction "A2_2") (pintype "passive"))
      (node (ref "Q12") (pin "3") (pinfunction "C_3") (pintype "passive"))
      (node (ref "U$64") (pin "11") (pinfunction "11_11") (pintype "passive"))
    )
    (net (code "76") (name "RELE13") (class "Default")
      (node (ref "D13") (pin "2") (pinfunction "A2_2") (pintype "passive"))
      (node (ref "Q13") (pin "3") (pinfunction "C_3") (pintype "passive"))
      (node (ref "U$65") (pin "11") (pinfunction "11_11") (pintype "passive"))
    )
    (net (code "77") (name "RELE14") (class "Default")
      (node (ref "D14") (pin "2") (pinfunction "A2_2") (pintype "passive"))
      (node (ref "Q14") (pin "3") (pinfunction "C_3") (pintype "passive"))
      (node (ref "U$66") (pin "11") (pinfunction "11_11") (pintype "passive"))
    )
    (net (code "78") (name "RELE15") (class "Default")
      (node (ref "D15") (pin "2") (pinfunction "A2_2") (pintype "passive"))
      (node (ref "Q15") (pin "3") (pinfunction "C_3") (pintype "passive"))
      (node (ref "U$67") (pin "11") (pinfunction "11_11") (pintype "passive"))
    )
    (net (code "79") (name "RELE16") (class "Default")
      (node (ref "D17") (pin "2") (pinfunction "A2_2") (pintype "passive"))
      (node (ref "Q16") (pin "3") (pinfunction "C_3") (pintype "passive"))
      (node (ref "U$68") (pin "11") (pinfunction "11_11") (pintype "passive"))
    )
    (net (code "80") (name "RST") (class "Default")
      (node (ref "U$1") (pin "RST") (pinfunction "RST_RST") (pintype "bidirectional"))
    )
    (net (code "81") (name "RST1") (class "Default")
      (node (ref "U$1") (pin "RST1") (pinfunction "RST1_RST1") (pintype "bidirectional"))
    )
    (net (code "82") (name "RVOLT") (class "Default")
      (node (ref "D1") (pin "3") (pinfunction "K_3") (pintype "passive"))
      (node (ref "D10") (pin "3") (pinfunction "K_3") (pintype "passive"))
      (node (ref "D11") (pin "3") (pinfunction "K_3") (pintype "passive"))
      (node (ref "D12") (pin "3") (pinfunction "K_3") (pintype "passive"))
      (node (ref "D13") (pin "3") (pinfunction "K_3") (pintype "passive"))
      (node (ref "D14") (pin "3") (pinfunction "K_3") (pintype "passive"))
      (node (ref "D15") (pin "3") (pinfunction "K_3") (pintype "passive"))
      (node (ref "D17") (pin "3") (pinfunction "K_3") (pintype "passive"))
      (node (ref "D2") (pin "3") (pinfunction "K_3") (pintype "passive"))
      (node (ref "D3") (pin "3") (pinfunction "K_3") (pintype "passive"))
      (node (ref "D4") (pin "3") (pinfunction "K_3") (pintype "passive"))
      (node (ref "D5") (pin "3") (pinfunction "K_3") (pintype "passive"))
      (node (ref "D6") (pin "3") (pinfunction "K_3") (pintype "passive"))
      (node (ref "D7") (pin "3") (pinfunction "K_3") (pintype "passive"))
      (node (ref "D8") (pin "3") (pinfunction "K_3") (pintype "passive"))
      (node (ref "D9") (pin "3") (pinfunction "K_3") (pintype "passive"))
      (node (ref "R2") (pin "1") (pinfunction "1_1") (pintype "passive"))
      (node (ref "R5") (pin "1") (pinfunction "1_1") (pintype "passive"))
      (node (ref "R6") (pin "1") (pinfunction "1_1") (pintype "passive"))
      (node (ref "R7") (pin "1") (pinfunction "1_1") (pintype "passive"))
      (node (ref "U$50") (pin "2") (pinfunction "2_2") (pintype "passive"))
      (node (ref "U$54") (pin "2") (pinfunction "2_2") (pintype "passive"))
      (node (ref "U$55") (pin "2") (pinfunction "2_2") (pintype "passive"))
      (node (ref "U$56") (pin "2") (pinfunction "2_2") (pintype "passive"))
      (node (ref "U$57") (pin "2") (pinfunction "2_2") (pintype "passive"))
      (node (ref "U$58") (pin "2") (pinfunction "2_2") (pintype "passive"))
      (node (ref "U$59") (pin "2") (pinfunction "2_2") (pintype "passive"))
      (node (ref "U$60") (pin "2") (pinfunction "2_2") (pintype "passive"))
      (node (ref "U$61") (pin "2") (pinfunction "2_2") (pintype "passive"))
      (node (ref "U$62") (pin "2") (pinfunction "2_2") (pintype "passive"))
      (node (ref "U$63") (pin "2") (pinfunction "2_2") (pintype "passive"))
      (node (ref "U$64") (pin "2") (pinfunction "2_2") (pintype "passive"))
      (node (ref "U$65") (pin "2") (pinfunction "2_2") (pintype "passive"))
      (node (ref "U$66") (pin "2") (pinfunction "2_2") (pintype "passive"))
      (node (ref "U$67") (pin "2") (pinfunction "2_2") (pintype "passive"))
      (node (ref "U$68") (pin "2") (pinfunction "2_2") (pintype "passive"))
    )
    (net (code "83") (name "RX") (class "Default")
      (node (ref "U$1") (pin "RX1") (pinfunction "RX1_RX1") (pintype "bidirectional"))
    )
    (net (code "84") (name "T1") (class "Default")
      (node (ref "IC1") (pin "15") (pinfunction "QA_15") (pintype "tri_state"))
      (node (ref "R8") (pin "1") (pinfunction "1_1") (pintype "passive"))
    )
    (net (code "85") (name "T2") (class "Default")
      (node (ref "IC1") (pin "1") (pinfunction "QB_1") (pintype "tri_state"))
      (node (ref "R9") (pin "1") (pinfunction "1_1") (pintype "passive"))
    )
    (net (code "86") (name "T3") (class "Default")
      (node (ref "IC1") (pin "2") (pinfunction "QC_2") (pintype "tri_state"))
      (node (ref "R10") (pin "1") (pinfunction "1_1") (pintype "passive"))
    )
    (net (code "87") (name "T4") (class "Default")
      (node (ref "IC1") (pin "3") (pinfunction "QD_3") (pintype "tri_state"))
      (node (ref "R11") (pin "1") (pinfunction "1_1") (pintype "passive"))
    )
    (net (code "88") (name "T5") (class "Default")
      (node (ref "IC1") (pin "4") (pinfunction "QE_4") (pintype "tri_state"))
      (node (ref "R12") (pin "1") (pinfunction "1_1") (pintype "passive"))
    )
    (net (code "89") (name "T6") (class "Default")
      (node (ref "IC1") (pin "5") (pinfunction "QF_5") (pintype "tri_state"))
      (node (ref "R13") (pin "1") (pinfunction "1_1") (pintype "passive"))
    )
    (net (code "90") (name "T7") (class "Default")
      (node (ref "IC1") (pin "6") (pinfunction "QG_6") (pintype "tri_state"))
      (node (ref "R14") (pin "1") (pinfunction "1_1") (pintype "passive"))
    )
    (net (code "91") (name "T8") (class "Default")
      (node (ref "IC1") (pin "7") (pinfunction "QH_7") (pintype "tri_state"))
      (node (ref "R15") (pin "1") (pinfunction "1_1") (pintype "passive"))
    )
    (net (code "92") (name "T9") (class "Default")
      (node (ref "IC2") (pin "15") (pinfunction "QA_15") (pintype "tri_state"))
      (node (ref "R23") (pin "1") (pinfunction "1_1") (pintype "passive"))
    )
    (net (code "93") (name "T10") (class "Default")
      (node (ref "IC2") (pin "1") (pinfunction "QB_1") (pintype "tri_state"))
      (node (ref "R22") (pin "1") (pinfunction "1_1") (pintype "passive"))
    )
    (net (code "94") (name "T11") (class "Default")
      (node (ref "IC2") (pin "2") (pinfunction "QC_2") (pintype "tri_state"))
      (node (ref "R21") (pin "1") (pinfunction "1_1") (pintype "passive"))
    )
    (net (code "95") (name "T12") (class "Default")
      (node (ref "IC2") (pin "3") (pinfunction "QD_3") (pintype "tri_state"))
      (node (ref "R20") (pin "1") (pinfunction "1_1") (pintype "passive"))
    )
    (net (code "96") (name "T13") (class "Default")
      (node (ref "IC2") (pin "4") (pinfunction "QE_4") (pintype "tri_state"))
      (node (ref "R19") (pin "1") (pinfunction "1_1") (pintype "passive"))
    )
    (net (code "97") (name "T14") (class "Default")
      (node (ref "IC2") (pin "5") (pinfunction "QF_5") (pintype "tri_state"))
      (node (ref "R18") (pin "1") (pinfunction "1_1") (pintype "passive"))
    )
    (net (code "98") (name "T15") (class "Default")
      (node (ref "IC2") (pin "6") (pinfunction "QG_6") (pintype "tri_state"))
      (node (ref "R17") (pin "1") (pinfunction "1_1") (pintype "passive"))
    )
    (net (code "99") (name "T16") (class "Default")
      (node (ref "IC2") (pin "7") (pinfunction "QH_7") (pintype "tri_state"))
      (node (ref "R16") (pin "1") (pinfunction "1_1") (pintype "passive"))
    )
    (net (code "100") (name "TX") (class "Default")
      (node (ref "U$1") (pin "TX0") (pinfunction "TX0_TX0") (pintype "bidirectional"))
    )
    (net (code "101") (name "VCC") (class "Default")
      (node (ref "IC1") (pin "10") (pinfunction "SCL_10") (pintype "input"))
      (node (ref "IC2") (pin "10") (pinfunction "SCL_10") (pintype "input"))
      (node (ref "R1") (pin "1") (pinfunction "1_1") (pintype "passive"))
      (node (ref "U$1") (pin "5V") (pinfunction "5.5V_5V") (pintype "bidirectional"))
    )
    (net (code "102") (name "unconnected-(D1-A1-Pad1)") (class "Default")
      (node (ref "D1") (pin "1") (pinfunction "A1_1") (pintype "passive"))
    )
    (net (code "103") (name "unconnected-(D2-A1-Pad1)") (class "Default")
      (node (ref "D2") (pin "1") (pinfunction "A1_1") (pintype "passive"))
    )
    (net (code "104") (name "unconnected-(D3-A1-Pad1)") (class "Default")
      (node (ref "D3") (pin "1") (pinfunction "A1_1") (pintype "passive"))
    )
    (net (code "105") (name "unconnected-(D4-A1-Pad1)") (class "Default")
      (node (ref "D4") (pin "1") (pinfunction "A1_1") (pintype "passive"))
    )
    (net (code "106") (name "unconnected-(D5-A1-Pad1)") (class "Default")
      (node (ref "D5") (pin "1") (pinfunction "A1_1") (pintype "passive"))
    )
    (net (code "107") (name "unconnected-(D6-A1-Pad1)") (class "Default")
      (node (ref "D6") (pin "1") (pinfunction "A1_1") (pintype "passive"))
    )
    (net (code "108") (name "unconnected-(D7-A1-Pad1)") (class "Default")
      (node (ref "D7") (pin "1") (pinfunction "A1_1") (pintype "passive"))
    )
    (net (code "109") (name "unconnected-(D8-A1-Pad1)") (class "Default")
      (node (ref "D8") (pin "1") (pinfunction "A1_1") (pintype "passive"))
    )
    (net (code "110") (name "unconnected-(D9-A1-Pad1)") (class "Default")
      (node (ref "D9") (pin "1") (pinfunction "A1_1") (pintype "passive"))
    )
    (net (code "111") (name "unconnected-(D10-A1-Pad1)") (class "Default")
      (node (ref "D10") (pin "1") (pinfunction "A1_1") (pintype "passive"))
    )
    (net (code "112") (name "unconnected-(D11-A1-Pad1)") (class "Default")
      (node (ref "D11") (pin "1") (pinfunction "A1_1") (pintype "passive"))
    )
    (net (code "113") (name "unconnected-(D12-A1-Pad1)") (class "Default")
      (node (ref "D12") (pin "1") (pinfunction "A1_1") (pintype "passive"))
    )
    (net (code "114") (name "unconnected-(D13-A1-Pad1)") (class "Default")
      (node (ref "D13") (pin "1") (pinfunction "A1_1") (pintype "passive"))
    )
    (net (code "115") (name "unconnected-(D14-A1-Pad1)") (class "Default")
      (node (ref "D14") (pin "1") (pinfunction "A1_1") (pintype "passive"))
    )
    (net (code "116") (name "unconnected-(D15-A1-Pad1)") (class "Default")
      (node (ref "D15") (pin "1") (pinfunction "A1_1") (pintype "passive"))
    )
    (net (code "117") (name "unconnected-(D17-A1-Pad1)") (class "Default")
      (node (ref "D17") (pin "1") (pinfunction "A1_1") (pintype "passive"))
    )
    (net (code "118") (name "unconnected-(IC2A-QH*-Pad9)") (class "Default")
      (node (ref "IC2") (pin "9") (pinfunction "QH*_9") (pintype "tri_state"))
    )
    (net (code "119") (name "unconnected-(U$1-PadICSP1)") (class "Default")
      (node (ref "U$1") (pin "ICSP1") (pinfunction "ICSP1_ICSP1") (pintype "bidirectional"))
    )
    (net (code "120") (name "unconnected-(U$1-PadICSP2)") (class "Default")
      (node (ref "U$1") (pin "ICSP2") (pinfunction "ICSP2_ICSP2") (pintype "bidirectional"))
    )
    (net (code "121") (name "unconnected-(U$1-PadICSP3)") (class "Default")
      (node (ref "U$1") (pin "ICSP3") (pinfunction "ICSP3_ICSP3") (pintype "bidirectional"))
    )
    (net (code "122") (name "unconnected-(U$1-PadICSP4)") (class "Default")
      (node (ref "U$1") (pin "ICSP4") (pinfunction "ICSP4_ICSP4") (pintype "bidirectional"))
    )
    (net (code "123") (name "unconnected-(U$1-PadICSP5)") (class "Default")
      (node (ref "U$1") (pin "ICSP5") (pinfunction "ICSP5_ICSP5") (pintype "bidirectional"))
    )
    (net (code "124") (name "unconnected-(U$1-PadICSP6)") (class "Default")
      (node (ref "U$1") (pin "ICSP6") (pinfunction "ICSP6_ICSP6") (pintype "bidirectional"))
    )
    (net (code "125") (name "unconnected-(U$50-Pad12)") (class "Default")
      (node (ref "U$50") (pin "12") (pinfunction "12_12") (pintype "passive"))
    )
    (net (code "126") (name "unconnected-(U$54-Pad12)") (class "Default")
      (node (ref "U$54") (pin "12") (pinfunction "12_12") (pintype "passive"))
    )
    (net (code "127") (name "unconnected-(U$55-Pad12)") (class "Default")
      (node (ref "U$55") (pin "12") (pinfunction "12_12") (pintype "passive"))
    )
    (net (code "128") (name "unconnected-(U$56-Pad12)") (class "Default")
      (node (ref "U$56") (pin "12") (pinfunction "12_12") (pintype "passive"))
    )
    (net (code "129") (name "unconnected-(U$57-Pad12)") (class "Default")
      (node (ref "U$57") (pin "12") (pinfunction "12_12") (pintype "passive"))
    )
    (net (code "130") (name "unconnected-(U$58-Pad12)") (class "Default")
      (node (ref "U$58") (pin "12") (pinfunction "12_12") (pintype "passive"))
    )
    (net (code "131") (name "unconnected-(U$59-Pad12)") (class "Default")
      (node (ref "U$59") (pin "12") (pinfunction "12_12") (pintype "passive"))
    )
    (net (code "132") (name "unconnected-(U$60-Pad12)") (class "Default")
      (node (ref "U$60") (pin "12") (pinfunction "12_12") (pintype "passive"))
    )
    (net (code "133") (name "unconnected-(U$61-Pad12)") (class "Default")
      (node (ref "U$61") (pin "12") (pinfunction "12_12") (pintype "passive"))
    )
    (net (code "134") (name "unconnected-(U$62-Pad12)") (class "Default")
      (node (ref "U$62") (pin "12") (pinfunction "12_12") (pintype "passive"))
    )
    (net (code "135") (name "unconnected-(U$63-Pad12)") (class "Default")
      (node (ref "U$63") (pin "12") (pinfunction "12_12") (pintype "passive"))
    )
    (net (code "136") (name "unconnected-(U$64-Pad12)") (class "Default")
      (node (ref "U$64") (pin "12") (pinfunction "12_12") (pintype "passive"))
    )
    (net (code "137") (name "unconnected-(U$65-Pad12)") (class "Default")
      (node (ref "U$65") (pin "12") (pinfunction "12_12") (pintype "passive"))
    )
    (net (code "138") (name "unconnected-(U$66-Pad12)") (class "Default")
      (node (ref "U$66") (pin "12") (pinfunction "12_12") (pintype "passive"))
    )
    (net (code "139") (name "unconnected-(U$67-Pad12)") (class "Default")
      (node (ref "U$67") (pin "12") (pinfunction "12_12") (pintype "passive"))
    )
    (net (code "140") (name "unconnected-(U$68-Pad12)") (class "Default")
      (node (ref "U$68") (pin "12") (pinfunction "12_12") (pintype "passive"))
    )
  )
)
